# Main_Board.net
KiCad netlist of a schematic drawn in EAGLE
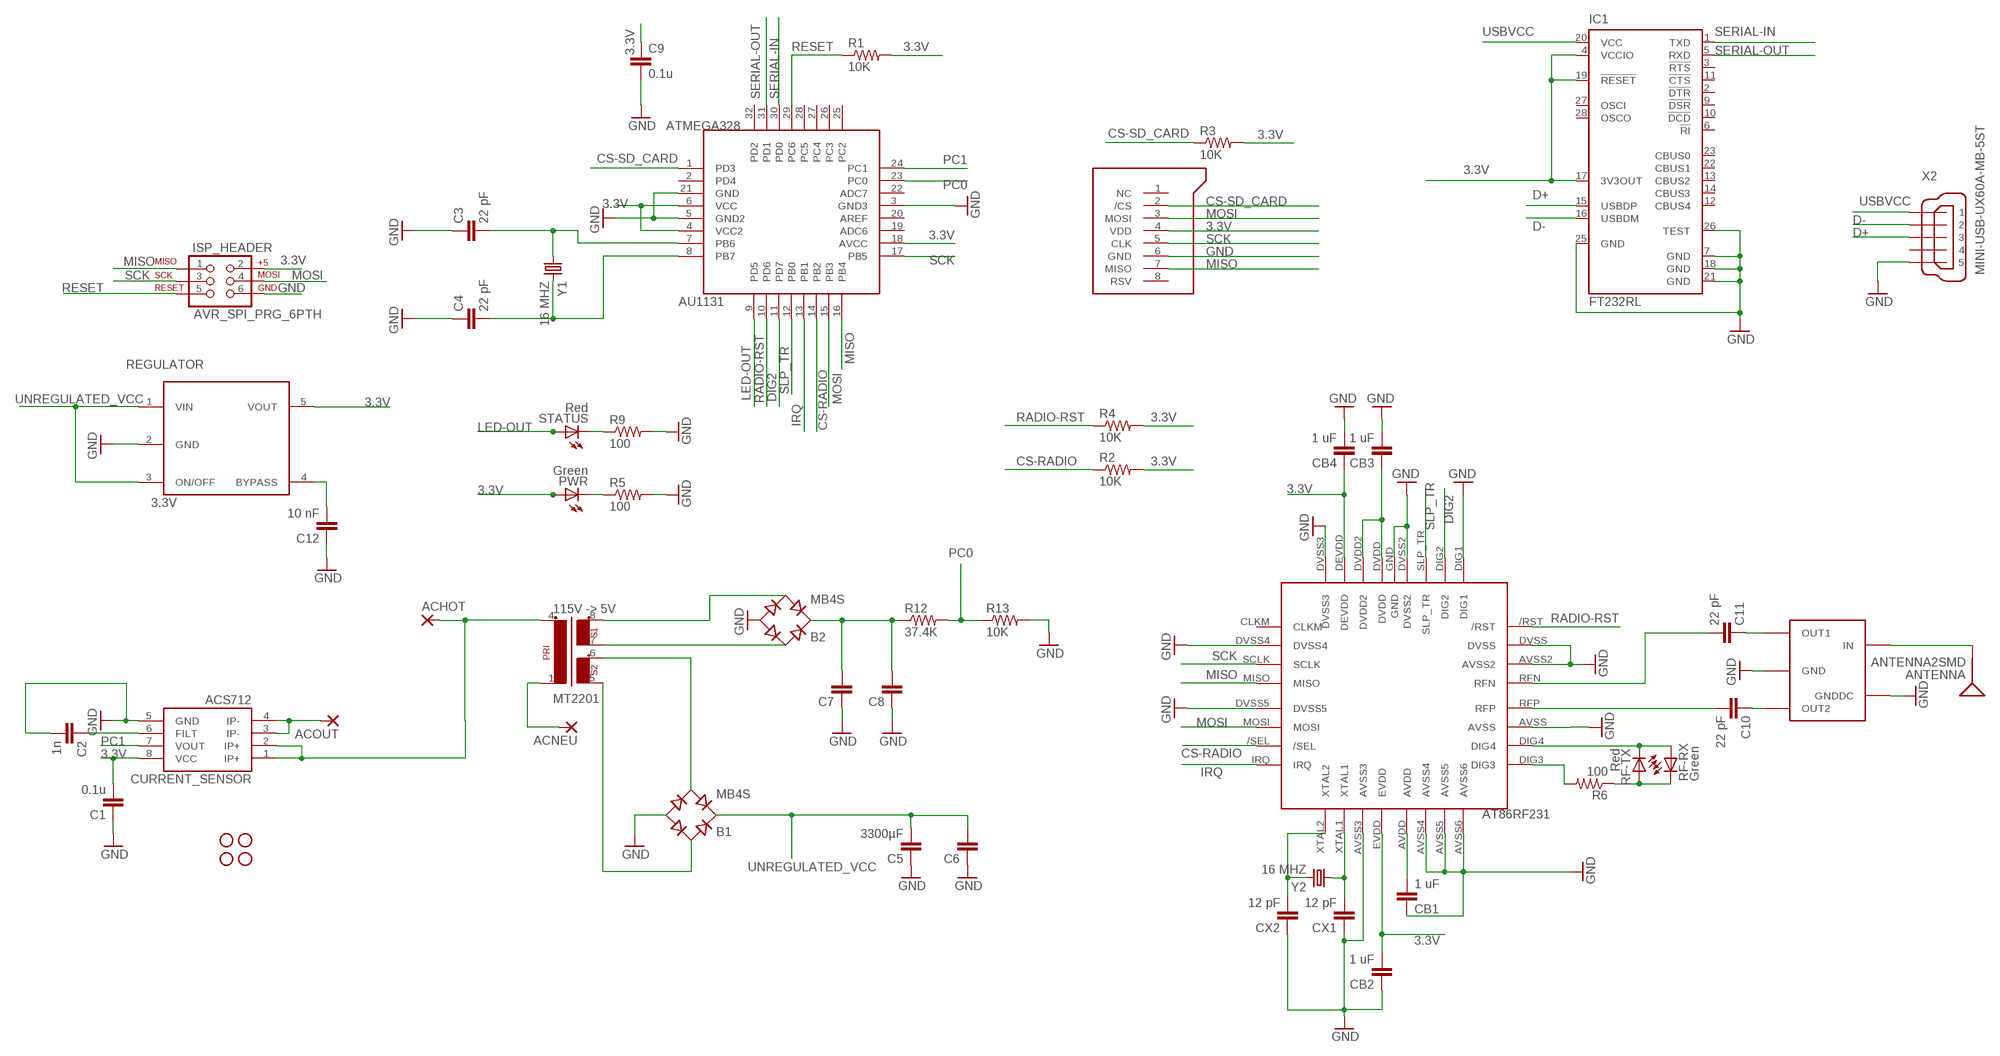
[diagram p0: schematic, sheet 1]

(export (version "E")
  (design (tool "Eeschema 10.0.6"))
  (components
    (comp (ref "3.3V_REGULATOR")
      (value "REG3.3V")
      (footprint "eagle-import:SOT23-5")
      (libsource (lib "eagle-import") (part "REG3.3V"))
    )
    (comp (ref "ACHOT")
      (value "PTH3MM")
      (footprint "eagle-import:PTH-3MM")
      (libsource (lib "eagle-import") (part "PTH3MM"))
    )
    (comp (ref "ACNEU")
      (value "PTH3MM")
      (footprint "eagle-import:PTH-3MM")
      (libsource (lib "eagle-import") (part "PTH3MM"))
    )
    (comp (ref "ACOUT")
      (value "PTH3MM")
      (footprint "eagle-import:PTH-3MM")
      (libsource (lib "eagle-import") (part "PTH3MM"))
    )
    (comp (ref "ANTENNA")
      (value "ANTENNA2SMD")
      (footprint "eagle-import:ANTENNA-CHIP2")
      (libsource (lib "eagle-import") (part "ANTENNA2SMD"))
    )
    (comp (ref "AT86RF231")
      (value "AT86RF231(RADIO)AT86RF231")
      (footprint "eagle-import:32QN2(RADIO)")
      (libsource (lib "eagle-import") (part "AT86RF231(RADIO)AT86RF231"))
    )
    (comp (ref "ATMEGA328")
      (value "ATMEGA32832A")
      (footprint "eagle-import:TQFP32-08")
      (libsource (lib "eagle-import") (part "ATMEGA32832A"))
    )
    (comp (ref "B1")
      (value "MB4S")
      (footprint "eagle-import:SOIC-4")
      (libsource (lib "eagle-import") (part "MBS4"))
    )
    (comp (ref "B2")
      (value "MB4S")
      (footprint "eagle-import:SOIC-4")
      (libsource (lib "eagle-import") (part "MBS4"))
    )
    (comp (ref "BALUN")
      (value "WE-BAL")
      (footprint "eagle-import:WE-BAL")
      (libsource (lib "eagle-import") (part "WE-BAL"))
    )
    (comp (ref "C1")
      (value "0.1u")
      (footprint "eagle-import:0603-CAP")
      (libsource (lib "eagle-import") (part "CAP0603-CAP"))
    )
    (comp (ref "C2")
      (value "1n")
      (footprint "eagle-import:0603-CAP")
      (libsource (lib "eagle-import") (part "CAP0603-CAP"))
    )
    (comp (ref "C3")
      (value "22 pF")
      (footprint "eagle-import:0603-CAP")
      (libsource (lib "eagle-import") (part "CAP0603-CAP"))
    )
    (comp (ref "C4")
      (value "22 pF")
      (footprint "eagle-import:0603-CAP")
      (libsource (lib "eagle-import") (part "CAP0603-CAP"))
    )
    (comp (ref "C5")
      (value "3300µF")
      (footprint "eagle-import:CAP-PTH-5MM")
      (libsource (lib "eagle-import") (part "CAPPTH1"))
    )
    (comp (ref "C6")
      (value "CAPPTH1")
      (footprint "eagle-import:CAP-PTH-5MM")
      (libsource (lib "eagle-import") (part "CAPPTH1"))
    )
    (comp (ref "C7")
      (value "CAPPTH1")
      (footprint "eagle-import:CAP-PTH-5MM")
      (libsource (lib "eagle-import") (part "CAPPTH1"))
    )
    (comp (ref "C8")
      (value "CAPPTH1")
      (footprint "eagle-import:CAP-PTH-5MM")
      (libsource (lib "eagle-import") (part "CAPPTH1"))
    )
    (comp (ref "C9")
      (value "0.1u")
      (footprint "eagle-import:0603-CAP")
      (libsource (lib "eagle-import") (part "CAP0603-CAP"))
    )
    (comp (ref "C10")
      (value "22 pF")
      (footprint "eagle-import:0603-CAP")
      (libsource (lib "eagle-import") (part "CAP0603-CAP"))
    )
    (comp (ref "C11")
      (value "22 pF")
      (footprint "eagle-import:0603-CAP")
      (libsource (lib "eagle-import") (part "CAP0603-CAP"))
    )
    (comp (ref "C12")
      (value "10 nF")
      (footprint "eagle-import:0603-CAP")
      (libsource (lib "eagle-import") (part "CAP0603-CAP"))
    )
    (comp (ref "CB1")
      (value "1 uF")
      (footprint "eagle-import:0603-CAP")
      (libsource (lib "eagle-import") (part "CAP0603-CAP"))
    )
    (comp (ref "CB2")
      (value "1 uF")
      (footprint "eagle-import:0603-CAP")
      (libsource (lib "eagle-import") (part "CAP0603-CAP"))
    )
    (comp (ref "CB3")
      (value "1 uF")
      (footprint "eagle-import:0603-CAP")
      (libsource (lib "eagle-import") (part "CAP0603-CAP"))
    )
    (comp (ref "CB4")
      (value "1 uF")
      (footprint "eagle-import:0603-CAP")
      (libsource (lib "eagle-import") (part "CAP0603-CAP"))
    )
    (comp (ref "CURRENT_SENSOR")
      (value "ACS712")
      (footprint "eagle-import:SO08")
      (libsource (lib "eagle-import") (part "ACS712"))
    )
    (comp (ref "CX1")
      (value "12 pF")
      (footprint "eagle-import:0603-CAP")
      (libsource (lib "eagle-import") (part "CAP0603-CAP"))
    )
    (comp (ref "CX2")
      (value "12 pF")
      (footprint "eagle-import:0603-CAP")
      (libsource (lib "eagle-import") (part "CAP0603-CAP"))
    )
    (comp (ref "IC1")
      (value "FT232RL")
      (footprint "eagle-import:SSOP28")
      (libsource (lib "eagle-import") (part "FT232RL"))
    )
    (comp (ref "ISP_HEADER")
      (value "AVR_SPI_PRG_6PTH")
      (footprint "eagle-import:2X3")
      (libsource (lib "eagle-import") (part "AVR_SPI_PRG_6PTH"))
    )
    (comp (ref "JP1")
      (value "STAND-OFF")
      (footprint "eagle-import:STAND-OFF")
      (libsource (lib "eagle-import") (part "STAND-OFF"))
    )
    (comp (ref "JP2")
      (value "STAND-OFF")
      (footprint "eagle-import:STAND-OFF")
      (libsource (lib "eagle-import") (part "STAND-OFF"))
    )
    (comp (ref "JP3")
      (value "STAND-OFF")
      (footprint "eagle-import:STAND-OFF")
      (libsource (lib "eagle-import") (part "STAND-OFF"))
    )
    (comp (ref "JP4")
      (value "STAND-OFF")
      (footprint "eagle-import:STAND-OFF")
      (libsource (lib "eagle-import") (part "STAND-OFF"))
    )
    (comp (ref "MICROSD")
      (value "MICROSD")
      (footprint "eagle-import:MICRO-SD-SOCKET-PP")
      (libsource (lib "eagle-import") (part "MICROSD"))
    )
    (comp (ref "MT2201")
      (value "115V -> 5V")
      (footprint "eagle-import:EI38-2")
      (libsource (lib "eagle-import") (part "EI38-2"))
    )
    (comp (ref "PWR")
      (value "Green")
      (footprint "eagle-import:LED-0603")
      (libsource (lib "eagle-import") (part "LED0603"))
    )
    (comp (ref "R1")
      (value "10K")
      (footprint "eagle-import:0603-RES")
      (libsource (lib "eagle-import") (part "RESISTOR0603-RES"))
    )
    (comp (ref "R2")
      (value "10K")
      (footprint "eagle-import:0603-RES")
      (libsource (lib "eagle-import") (part "RESISTOR0603-RES"))
    )
    (comp (ref "R3")
      (value "10K")
      (footprint "eagle-import:0603-RES")
      (libsource (lib "eagle-import") (part "RESISTOR0603-RES"))
    )
    (comp (ref "R4")
      (value "10K")
      (footprint "eagle-import:0603-RES")
      (libsource (lib "eagle-import") (part "RESISTOR0603-RES"))
    )
    (comp (ref "R5")
      (value "100")
      (footprint "eagle-import:0603-RES")
      (libsource (lib "eagle-import") (part "RESISTOR0603-RES"))
    )
    (comp (ref "R6")
      (value "100")
      (footprint "eagle-import:0603-RES")
      (libsource (lib "eagle-import") (part "RESISTOR0603-RES"))
    )
    (comp (ref "R9")
      (value "100")
      (footprint "eagle-import:0603-RES")
      (libsource (lib "eagle-import") (part "RESISTOR0603-RES"))
    )
    (comp (ref "R12")
      (value "37.4K")
      (footprint "eagle-import:0603-RES")
      (libsource (lib "eagle-import") (part "RESISTOR0603-RES"))
    )
    (comp (ref "R13")
      (value "10K")
      (footprint "eagle-import:0603-RES")
      (libsource (lib "eagle-import") (part "RESISTOR0603-RES"))
    )
    (comp (ref "RF-RX")
      (value "Green")
      (footprint "eagle-import:LED-0603")
      (libsource (lib "eagle-import") (part "LED0603"))
    )
    (comp (ref "RF-TX")
      (value "Red")
      (footprint "eagle-import:LED-0603")
      (libsource (lib "eagle-import") (part "LED0603"))
    )
    (comp (ref "STATUS")
      (value "Red")
      (footprint "eagle-import:LED-0603")
      (libsource (lib "eagle-import") (part "LED0603"))
    )
    (comp (ref "X2")
      (value "MINI-USB-UX60A-MB-5ST")
      (footprint "eagle-import:UX60A-MB-5ST")
      (libsource (lib "eagle-import") (part "MINI-USB-UX60A-MB-5ST"))
    )
    (comp (ref "Y1")
      (value "16 MHZ")
      (footprint "eagle-import:HC49UP")
      (libsource (lib "eagle-import") (part "CRYSTALSMD"))
    )
    (comp (ref "Y2")
      (value "16 MHZ")
      (footprint "eagle-import:HC49UP")
      (libsource (lib "eagle-import") (part "CRYSTALSMD"))
    )
  )
  (nets
    (net (code "1") (name "/3.3V") (class "Default")
      (node (ref "3.3V_REGULATOR") (pin "5") (pinfunction "VOUT_5") (pintype "bidirectional"))
      (node (ref "AT86RF231") (pin "DEVDD") (pinfunction "DEVDD_DEVDD") (pintype "bidirectional"))
      (node (ref "AT86RF231") (pin "EVDD") (pinfunction "EVDD_EVDD") (pintype "bidirectional"))
      (node (ref "ATMEGA328") (pin "18") (pinfunction "AVCC_18") (pintype "bidirectional"))
      (node (ref "ATMEGA328") (pin "4") (pinfunction "VCC2_4") (pintype "bidirectional"))
      (node (ref "ATMEGA328") (pin "6") (pinfunction "VCC_6") (pintype "bidirectional"))
      (node (ref "C1") (pin "2") (pinfunction "2_2") (pintype "passive"))
      (node (ref "C9") (pin "1") (pinfunction "1_1") (pintype "passive"))
      (node (ref "CB2") (pin "2") (pinfunction "2_2") (pintype "passive"))
      (node (ref "CB4") (pin "1") (pinfunction "1_1") (pintype "passive"))
      (node (ref "CURRENT_SENSOR") (pin "8") (pinfunction "VCC_8") (pintype "bidirectional"))
      (node (ref "IC1") (pin "17") (pinfunction "3V3OUT_17") (pintype "output"))
      (node (ref "IC1") (pin "19") (pinfunction "~{RESET}_19") (pintype "input"))
      (node (ref "IC1") (pin "4") (pinfunction "VCCIO_4") (pintype "power_in"))
      (node (ref "ISP_HEADER") (pin "2") (pinfunction "2_2") (pintype "passive"))
      (node (ref "MICROSD") (pin "4") (pinfunction "VDD_4") (pintype "bidirectional"))
      (node (ref "PWR") (pin "A") (pinfunction "A_A") (pintype "passive"))
      (node (ref "R1") (pin "2") (pinfunction "2_2") (pintype "passive"))
      (node (ref "R2") (pin "2") (pinfunction "2_2") (pintype "passive"))
      (node (ref "R3") (pin "2") (pinfunction "2_2") (pintype "passive"))
      (node (ref "R4") (pin "2") (pinfunction "2_2") (pintype "passive"))
    )
    (net (code "2") (name "/CS-RADIO") (class "Default")
      (node (ref "AT86RF231") (pin "/SEL") (pinfunction "/SEL_/SEL") (pintype "bidirectional"))
      (node (ref "ATMEGA328") (pin "14") (pinfunction "PB2_14") (pintype "bidirectional"))
      (node (ref "R2") (pin "1") (pinfunction "1_1") (pintype "passive"))
    )
    (net (code "3") (name "/CS-SD_CARD") (class "Default")
      (node (ref "ATMEGA328") (pin "1") (pinfunction "PD3_1") (pintype "bidirectional"))
      (node (ref "MICROSD") (pin "2") (pinfunction "/CS_2") (pintype "bidirectional"))
      (node (ref "R3") (pin "1") (pinfunction "1_1") (pintype "passive"))
    )
    (net (code "4") (name "/D+") (class "Default")
      (node (ref "IC1") (pin "15") (pinfunction "USBDP_15") (pintype "bidirectional"))
      (node (ref "X2") (pin "3") (pinfunction "3_3") (pintype "input"))
    )
    (net (code "5") (name "/D-") (class "Default")
      (node (ref "IC1") (pin "16") (pinfunction "USBDM_16") (pintype "bidirectional"))
      (node (ref "X2") (pin "2") (pinfunction "2_2") (pintype "input"))
    )
    (net (code "6") (name "/DIG2") (class "Default")
      (node (ref "AT86RF231") (pin "DIG2") (pinfunction "DIG2_DIG2") (pintype "bidirectional"))
      (node (ref "ATMEGA328") (pin "11") (pinfunction "PD7_11") (pintype "bidirectional"))
    )
    (net (code "7") (name "/IRQ") (class "Default")
      (node (ref "AT86RF231") (pin "IRQ") (pinfunction "IRQ_IRQ") (pintype "bidirectional"))
      (node (ref "ATMEGA328") (pin "13") (pinfunction "PB1_13") (pintype "bidirectional"))
    )
    (net (code "8") (name "/LED-OUT") (class "Default")
      (node (ref "ATMEGA328") (pin "9") (pinfunction "PD5_9") (pintype "bidirectional"))
      (node (ref "STATUS") (pin "A") (pinfunction "A_A") (pintype "passive"))
    )
    (net (code "9") (name "/MISO") (class "Default")
      (node (ref "AT86RF231") (pin "MISO") (pinfunction "MISO_MISO") (pintype "bidirectional"))
      (node (ref "ATMEGA328") (pin "16") (pinfunction "PB4_16") (pintype "bidirectional"))
      (node (ref "ISP_HEADER") (pin "1") (pinfunction "1_1") (pintype "passive"))
      (node (ref "MICROSD") (pin "7") (pinfunction "MISO_7") (pintype "bidirectional"))
    )
    (net (code "10") (name "/MOSI") (class "Default")
      (node (ref "AT86RF231") (pin "MOSI") (pinfunction "MOSI_MOSI") (pintype "bidirectional"))
      (node (ref "ATMEGA328") (pin "15") (pinfunction "PB3_15") (pintype "bidirectional"))
      (node (ref "ISP_HEADER") (pin "4") (pinfunction "4_4") (pintype "passive"))
      (node (ref "MICROSD") (pin "3") (pinfunction "MOSI_3") (pintype "bidirectional"))
    )
    (net (code "11") (name "/PC0") (class "Default")
      (node (ref "ATMEGA328") (pin "23") (pinfunction "PC0_23") (pintype "bidirectional"))
      (node (ref "R12") (pin "2") (pinfunction "2_2") (pintype "passive"))
      (node (ref "R13") (pin "1") (pinfunction "1_1") (pintype "passive"))
    )
    (net (code "12") (name "/PC1") (class "Default")
      (node (ref "ATMEGA328") (pin "24") (pinfunction "PC1_24") (pintype "bidirectional"))
      (node (ref "CURRENT_SENSOR") (pin "7") (pinfunction "VOUT_7") (pintype "bidirectional"))
    )
    (net (code "13") (name "/RADIO-RST") (class "Default")
      (node (ref "AT86RF231") (pin "/RST") (pinfunction "/RST_/RST") (pintype "bidirectional"))
      (node (ref "ATMEGA328") (pin "10") (pinfunction "PD6_10") (pintype "bidirectional"))
      (node (ref "R4") (pin "1") (pinfunction "1_1") (pintype "passive"))
    )
    (net (code "14") (name "/RESET") (class "Default")
      (node (ref "ATMEGA328") (pin "29") (pinfunction "PC6_29") (pintype "bidirectional"))
      (node (ref "ISP_HEADER") (pin "5") (pinfunction "5_5") (pintype "passive"))
      (node (ref "R1") (pin "1") (pinfunction "1_1") (pintype "passive"))
    )
    (net (code "15") (name "/SCK") (class "Default")
      (node (ref "AT86RF231") (pin "SCLK") (pinfunction "SCLK_SCLK") (pintype "bidirectional"))
      (node (ref "ATMEGA328") (pin "17") (pinfunction "PB5_17") (pintype "bidirectional"))
      (node (ref "ISP_HEADER") (pin "3") (pinfunction "3_3") (pintype "passive"))
      (node (ref "MICROSD") (pin "5") (pinfunction "CLK_5") (pintype "bidirectional"))
    )
    (net (code "16") (name "/SERIAL-IN") (class "Default")
      (node (ref "ATMEGA328") (pin "30") (pinfunction "PD0_30") (pintype "bidirectional"))
      (node (ref "IC1") (pin "1") (pinfunction "TXD_1") (pintype "output"))
    )
    (net (code "17") (name "/SERIAL-OUT") (class "Default")
      (node (ref "ATMEGA328") (pin "31") (pinfunction "PD1_31") (pintype "bidirectional"))
      (node (ref "IC1") (pin "5") (pinfunction "RXD_5") (pintype "input"))
    )
    (net (code "18") (name "/SLP_TR") (class "Default")
      (node (ref "AT86RF231") (pin "SLP_TR") (pinfunction "SLP_TR_SLP_TR") (pintype "bidirectional"))
      (node (ref "ATMEGA328") (pin "12") (pinfunction "PB0_12") (pintype "bidirectional"))
    )
    (net (code "19") (name "/UNREGULATED_VCC") (class "Default")
      (node (ref "3.3V_REGULATOR") (pin "1") (pinfunction "VIN_1") (pintype "bidirectional"))
      (node (ref "3.3V_REGULATOR") (pin "3") (pinfunction "ON/OFF_3") (pintype "bidirectional"))
      (node (ref "B1") (pin "+") (pinfunction "+_+") (pintype "passive"))
      (node (ref "C5") (pin "2") (pinfunction "2_2") (pintype "passive"))
      (node (ref "C6") (pin "2") (pinfunction "2_2") (pintype "passive"))
    )
    (net (code "20") (name "/USBVCC") (class "Default")
      (node (ref "IC1") (pin "20") (pinfunction "VCC_20") (pintype "power_in"))
      (node (ref "X2") (pin "1") (pinfunction "1_1") (pintype "input"))
    )
    (net (code "21") (name "GND") (class "Default")
      (node (ref "3.3V_REGULATOR") (pin "2") (pinfunction "GND_2") (pintype "bidirectional"))
      (node (ref "AT86RF231") (pin "AVSS") (pinfunction "AVSS_AVSS") (pintype "bidirectional"))
      (node (ref "AT86RF231") (pin "AVSS2") (pinfunction "AVSS2_AVSS2") (pintype "bidirectional"))
      (node (ref "AT86RF231") (pin "AVSS3") (pinfunction "AVSS3_AVSS3") (pintype "bidirectional"))
      (node (ref "AT86RF231") (pin "AVSS4") (pinfunction "AVSS4_AVSS4") (pintype "bidirectional"))
      (node (ref "AT86RF231") (pin "AVSS5") (pinfunction "AVSS5_AVSS5") (pintype "bidirectional"))
      (node (ref "AT86RF231") (pin "AVSS6") (pinfunction "AVSS6_AVSS6") (pintype "bidirectional"))
      (node (ref "AT86RF231") (pin "DIG1") (pinfunction "DIG1_DIG1") (pintype "bidirectional"))
      (node (ref "AT86RF231") (pin "DVSS") (pinfunction "DVSS_DVSS") (pintype "bidirectional"))
      (node (ref "AT86RF231") (pin "DVSS2") (pinfunction "DVSS2_DVSS2") (pintype "bidirectional"))
      (node (ref "AT86RF231") (pin "DVSS3") (pinfunction "DVSS3_DVSS3") (pintype "bidirectional"))
      (node (ref "AT86RF231") (pin "DVSS4") (pinfunction "DVSS4_DVSS4") (pintype "bidirectional"))
      (node (ref "AT86RF231") (pin "DVSS5") (pinfunction "DVSS5_DVSS5") (pintype "bidirectional"))
      (node (ref "AT86RF231") (pin "GND") (pinfunction "GND_GND") (pintype "bidirectional"))
      (node (ref "ATMEGA328") (pin "21") (pinfunction "GND_21") (pintype "bidirectional"))
      (node (ref "ATMEGA328") (pin "3") (pinfunction "GND3_3") (pintype "bidirectional"))
      (node (ref "ATMEGA328") (pin "5") (pinfunction "GND2_5") (pintype "bidirectional"))
      (node (ref "B1") (pin "-") (pinfunction "-_-") (pintype "passive"))
      (node (ref "B2") (pin "-") (pinfunction "-_-") (pintype "passive"))
      (node (ref "BALUN") (pin "GND") (pinfunction "GND_GND") (pintype "bidirectional"))
      (node (ref "BALUN") (pin "GNDDC") (pinfunction "GNDDC_GNDDC") (pintype "bidirectional"))
      (node (ref "C1") (pin "1") (pinfunction "1_1") (pintype "passive"))
      (node (ref "C12") (pin "1") (pinfunction "1_1") (pintype "passive"))
      (node (ref "C2") (pin "2") (pinfunction "2_2") (pintype "passive"))
      (node (ref "C3") (pin "1") (pinfunction "1_1") (pintype "passive"))
      (node (ref "C4") (pin "1") (pinfunction "1_1") (pintype "passive"))
      (node (ref "C5") (pin "1") (pinfunction "1_1") (pintype "passive"))
      (node (ref "C6") (pin "1") (pinfunction "1_1") (pintype "passive"))
      (node (ref "C7") (pin "1") (pinfunction "1_1") (pintype "passive"))
      (node (ref "C8") (pin "1") (pinfunction "1_1") (pintype "passive"))
      (node (ref "C9") (pin "2") (pinfunction "2_2") (pintype "passive"))
      (node (ref "CB1") (pin "1") (pinfunction "1_1") (pintype "passive"))
      (node (ref "CB2") (pin "1") (pinfunction "1_1") (pintype "passive"))
      (node (ref "CB3") (pin "2") (pinfunction "2_2") (pintype "passive"))
      (node (ref "CB4") (pin "2") (pinfunction "2_2") (pintype "passive"))
      (node (ref "CURRENT_SENSOR") (pin "5") (pinfunction "GND_5") (pintype "bidirectional"))
      (node (ref "CX1") (pin "1") (pinfunction "1_1") (pintype "passive"))
      (node (ref "CX2") (pin "1") (pinfunction "1_1") (pintype "passive"))
      (node (ref "IC1") (pin "18") (pinfunction "GND_18") (pintype "power_in"))
      (node (ref "IC1") (pin "21") (pinfunction "GND_21") (pintype "power_in"))
      (node (ref "IC1") (pin "25") (pinfunction "GND_25") (pintype "power_in"))
      (node (ref "IC1") (pin "26") (pinfunction "TEST_26") (pintype "input"))
      (node (ref "IC1") (pin "7") (pinfunction "GND_7") (pintype "power_in"))
      (node (ref "ISP_HEADER") (pin "6") (pinfunction "6_6") (pintype "passive"))
      (node (ref "MICROSD") (pin "6") (pinfunction "GND_6") (pintype "bidirectional"))
      (node (ref "R13") (pin "2") (pinfunction "2_2") (pintype "passive"))
      (node (ref "R5") (pin "2") (pinfunction "2_2") (pintype "passive"))
      (node (ref "R9") (pin "2") (pinfunction "2_2") (pintype "passive"))
      (node (ref "X2") (pin "5") (pinfunction "5_5") (pintype "input"))
    )
    (net (code "22") (name "Net-(3.3V_REGULATOR-BYPASS)") (class "Default")
      (node (ref "3.3V_REGULATOR") (pin "4") (pinfunction "BYPASS_4") (pintype "bidirectional"))
      (node (ref "C12") (pin "2") (pinfunction "2_2") (pintype "passive"))
    )
    (net (code "23") (name "Net-(ACHOT-P)") (class "Default")
      (node (ref "ACHOT") (pin "1") (pinfunction "P_1") (pintype "passive"))
      (node (ref "CURRENT_SENSOR") (pin "1") (pinfunction "IP+_1") (pintype "bidirectional"))
      (node (ref "CURRENT_SENSOR") (pin "2") (pinfunction "IP+_2") (pintype "bidirectional"))
      (node (ref "MT2201") (pin "4") (pinfunction "4_4") (pintype "passive"))
    )
    (net (code "24") (name "Net-(ACNEU-P)") (class "Default")
      (node (ref "ACNEU") (pin "1") (pinfunction "P_1") (pintype "passive"))
      (node (ref "MT2201") (pin "1") (pinfunction "1_1") (pintype "passive"))
    )
    (net (code "25") (name "Net-(ACOUT-P)") (class "Default")
      (node (ref "ACOUT") (pin "1") (pinfunction "P_1") (pintype "passive"))
      (node (ref "CURRENT_SENSOR") (pin "3") (pinfunction "IP-_3") (pintype "bidirectional"))
      (node (ref "CURRENT_SENSOR") (pin "4") (pinfunction "IP-_4") (pintype "bidirectional"))
    )
    (net (code "26") (name "Net-(ANTENNA-SIGNAL)") (class "Default")
      (node (ref "ANTENNA") (pin "FEED") (pinfunction "SIGNAL_FEED") (pintype "bidirectional"))
      (node (ref "BALUN") (pin "IN") (pinfunction "IN_IN") (pintype "bidirectional"))
    )
    (net (code "27") (name "Net-(AT86RF231-PadAVDD)") (class "Default")
      (node (ref "AT86RF231") (pin "AVDD") (pinfunction "AVDD_AVDD") (pintype "bidirectional"))
      (node (ref "CB1") (pin "2") (pinfunction "2_2") (pintype "passive"))
    )
    (net (code "28") (name "Net-(AT86RF231-PadDIG3)") (class "Default")
      (node (ref "AT86RF231") (pin "DIG3") (pinfunction "DIG3_DIG3") (pintype "bidirectional"))
      (node (ref "R6") (pin "2") (pinfunction "2_2") (pintype "passive"))
    )
    (net (code "29") (name "Net-(AT86RF231-PadDIG4)") (class "Default")
      (node (ref "AT86RF231") (pin "DIG4") (pinfunction "DIG4_DIG4") (pintype "bidirectional"))
      (node (ref "RF-RX") (pin "A") (pinfunction "A_A") (pintype "passive"))
      (node (ref "RF-TX") (pin "C") (pinfunction "C_C") (pintype "passive"))
    )
    (net (code "30") (name "Net-(AT86RF231-PadDVDD)") (class "Default")
      (node (ref "AT86RF231") (pin "DVDD") (pinfunction "DVDD_DVDD") (pintype "bidirectional"))
      (node (ref "AT86RF231") (pin "DVDD2") (pinfunction "DVDD2_DVDD2") (pintype "bidirectional"))
      (node (ref "CB3") (pin "1") (pinfunction "1_1") (pintype "passive"))
    )
    (net (code "31") (name "Net-(AT86RF231-PadRFN)") (class "Default")
      (node (ref "AT86RF231") (pin "RFN") (pinfunction "RFN_RFN") (pintype "bidirectional"))
      (node (ref "C11") (pin "2") (pinfunction "2_2") (pintype "passive"))
    )
    (net (code "32") (name "Net-(AT86RF231-PadRFP)") (class "Default")
      (node (ref "AT86RF231") (pin "RFP") (pinfunction "RFP_RFP") (pintype "bidirectional"))
      (node (ref "C10") (pin "2") (pinfunction "2_2") (pintype "passive"))
    )
    (net (code "33") (name "Net-(AT86RF231-PadXTAL1)") (class "Default")
      (node (ref "AT86RF231") (pin "XTAL1") (pinfunction "XTAL1_XTAL1") (pintype "bidirectional"))
      (node (ref "CX1") (pin "2") (pinfunction "2_2") (pintype "passive"))
      (node (ref "Y2") (pin "1") (pinfunction "1_1") (pintype "passive"))
    )
    (net (code "34") (name "Net-(AT86RF231-PadXTAL2)") (class "Default")
      (node (ref "AT86RF231") (pin "XTAL2") (pinfunction "XTAL2_XTAL2") (pintype "bidirectional"))
      (node (ref "CX2") (pin "2") (pinfunction "2_2") (pintype "passive"))
      (node (ref "Y2") (pin "2") (pinfunction "2_2") (pintype "passive"))
    )
    (net (code "35") (name "Net-(ATMEGA328-PB6)") (class "Default")
      (node (ref "ATMEGA328") (pin "7") (pinfunction "PB6_7") (pintype "bidirectional"))
      (node (ref "C3") (pin "2") (pinfunction "2_2") (pintype "passive"))
      (node (ref "Y1") (pin "1") (pinfunction "1_1") (pintype "passive"))
    )
    (net (code "36") (name "Net-(ATMEGA328-PB7)") (class "Default")
      (node (ref "ATMEGA328") (pin "8") (pinfunction "PB7_8") (pintype "bidirectional"))
      (node (ref "C4") (pin "2") (pinfunction "2_2") (pintype "passive"))
      (node (ref "Y1") (pin "2") (pinfunction "2_2") (pintype "passive"))
    )
    (net (code "37") (name "Net-(B1-AC1)") (class "Default")
      (node (ref "B1") (pin "~1") (pinfunction "AC1_~1") (pintype "passive"))
      (node (ref "MT2201") (pin "5") (pinfunction "5_5") (pintype "passive"))
    )
    (net (code "38") (name "Net-(B1-AC2)") (class "Default")
      (node (ref "B1") (pin "~2") (pinfunction "AC2_~2") (pintype "passive"))
      (node (ref "MT2201") (pin "6") (pinfunction "6_6") (pintype "passive"))
    )
    (net (code "39") (name "Net-(B2-AC1)") (class "Default")
      (node (ref "B2") (pin "~1") (pinfunction "AC1_~1") (pintype "passive"))
      (node (ref "MT2201") (pin "7") (pinfunction "7_7") (pintype "passive"))
    )
    (net (code "40") (name "Net-(B2-AC2)") (class "Default")
      (node (ref "B2") (pin "~2") (pinfunction "AC2_~2") (pintype "passive"))
      (node (ref "MT2201") (pin "8") (pinfunction "8_8") (pintype "passive"))
    )
    (net (code "41") (name "Net-(B2-Pad+)") (class "Default")
      (node (ref "B2") (pin "+") (pinfunction "+_+") (pintype "passive"))
      (node (ref "C7") (pin "2") (pinfunction "2_2") (pintype "passive"))
      (node (ref "C8") (pin "2") (pinfunction "2_2") (pintype "passive"))
      (node (ref "R12") (pin "1") (pinfunction "1_1") (pintype "passive"))
    )
    (net (code "42") (name "Net-(BALUN-PadOUT1)") (class "Default")
      (node (ref "BALUN") (pin "OUT1") (pinfunction "OUT1_OUT1") (pintype "bidirectional"))
      (node (ref "C11") (pin "1") (pinfunction "1_1") (pintype "passive"))
    )
    (net (code "43") (name "Net-(BALUN-PadOUT2)") (class "Default")
      (node (ref "BALUN") (pin "OUT2") (pinfunction "OUT2_OUT2") (pintype "bidirectional"))
      (node (ref "C10") (pin "1") (pinfunction "1_1") (pintype "passive"))
    )
    (net (code "44") (name "Net-(CURRENT_SENSOR-FILT)") (class "Default")
      (node (ref "C2") (pin "1") (pinfunction "1_1") (pintype "passive"))
      (node (ref "CURRENT_SENSOR") (pin "6") (pinfunction "FILT_6") (pintype "bidirectional"))
    )
    (net (code "45") (name "Net-(PWR-PadC)") (class "Default")
      (node (ref "PWR") (pin "C") (pinfunction "C_C") (pintype "passive"))
      (node (ref "R5") (pin "1") (pinfunction "1_1") (pintype "passive"))
    )
    (net (code "46") (name "Net-(R6-Pad1)") (class "Default")
      (node (ref "R6") (pin "1") (pinfunction "1_1") (pintype "passive"))
      (node (ref "RF-RX") (pin "C") (pinfunction "C_C") (pintype "passive"))
      (node (ref "RF-TX") (pin "A") (pinfunction "A_A") (pintype "passive"))
    )
    (net (code "47") (name "Net-(R9-Pad1)") (class "Default")
      (node (ref "R9") (pin "1") (pinfunction "1_1") (pintype "passive"))
      (node (ref "STATUS") (pin "C") (pinfunction "C_C") (pintype "passive"))
    )
    (net (code "48") (name "unconnected-(AT86RF231-PadCLKM)") (class "Default")
      (node (ref "AT86RF231") (pin "CLKM") (pinfunction "CLKM_CLKM") (pintype "bidirectional"))
    )
    (net (code "49") (name "unconnected-(ATMEGA328-ADC6-Pad19)") (class "Default")
      (node (ref "ATMEGA328") (pin "19") (pinfunction "ADC6_19") (pintype "bidirectional"))
    )
    (net (code "50") (name "unconnected-(ATMEGA328-ADC7-Pad22)") (class "Default")
      (node (ref "ATMEGA328") (pin "22") (pinfunction "ADC7_22") (pintype "bidirectional"))
    )
    (net (code "51") (name "unconnected-(ATMEGA328-AREF-Pad20)") (class "Default")
      (node (ref "ATMEGA328") (pin "20") (pinfunction "AREF_20") (pintype "bidirectional"))
    )
    (net (code "52") (name "unconnected-(ATMEGA328-PC2-Pad25)") (class "Default")
      (node (ref "ATMEGA328") (pin "25") (pinfunction "PC2_25") (pintype "bidirectional"))
    )
    (net (code "53") (name "unconnected-(ATMEGA328-PC3-Pad26)") (class "Default")
      (node (ref "ATMEGA328") (pin "26") (pinfunction "PC3_26") (pintype "bidirectional"))
    )
    (net (code "54") (name "unconnected-(ATMEGA328-PC4-Pad27)") (class "Default")
      (node (ref "ATMEGA328") (pin "27") (pinfunction "PC4_27") (pintype "bidirectional"))
    )
    (net (code "55") (name "unconnected-(ATMEGA328-PC5-Pad28)") (class "Default")
      (node (ref "ATMEGA328") (pin "28") (pinfunction "PC5_28") (pintype "bidirectional"))
    )
    (net (code "56") (name "unconnected-(ATMEGA328-PD2-Pad32)") (class "Default")
      (node (ref "ATMEGA328") (pin "32") (pinfunction "PD2_32") (pintype "bidirectional"))
    )
    (net (code "57") (name "unconnected-(ATMEGA328-PD4-Pad2)") (class "Default")
      (node (ref "ATMEGA328") (pin "2") (pinfunction "PD4_2") (pintype "bidirectional"))
    )
    (net (code "58") (name "unconnected-(IC1-CBUS0-Pad23)") (class "Default")
      (node (ref "IC1") (pin "23") (pinfunction "CBUS0_23") (pintype "bidirectional"))
    )
    (net (code "59") (name "unconnected-(IC1-CBUS1-Pad22)") (class "Default")
      (node (ref "IC1") (pin "22") (pinfunction "CBUS1_22") (pintype "bidirectional"))
    )
    (net (code "60") (name "unconnected-(IC1-CBUS2-Pad13)") (class "Default")
      (node (ref "IC1") (pin "13") (pinfunction "CBUS2_13") (pintype "bidirectional"))
    )
    (net (code "61") (name "unconnected-(IC1-CBUS3-Pad14)") (class "Default")
      (node (ref "IC1") (pin "14") (pinfunction "CBUS3_14") (pintype "bidirectional"))
    )
    (net (code "62") (name "unconnected-(IC1-CBUS4-Pad12)") (class "Default")
      (node (ref "IC1") (pin "12") (pinfunction "CBUS4_12") (pintype "bidirectional"))
    )
    (net (code "63") (name "unconnected-(IC1-OSCI-Pad27)") (class "Default")
      (node (ref "IC1") (pin "27") (pinfunction "OSCI_27") (pintype "input"))
    )
    (net (code "64") (name "unconnected-(IC1-OSCO-Pad28)") (class "Default")
      (node (ref "IC1") (pin "28") (pinfunction "OSCO_28") (pintype "output"))
    )
    (net (code "65") (name "unconnected-(IC1-~{CTS}-Pad11)") (class "Default")
      (node (ref "IC1") (pin "11") (pinfunction "~{CTS}_11") (pintype "input"))
    )
    (net (code "66") (name "unconnected-(IC1-~{DCD}-Pad10)") (class "Default")
      (node (ref "IC1") (pin "10") (pinfunction "~{DCD}_10") (pintype "input"))
    )
    (net (code "67") (name "unconnected-(IC1-~{DSR}-Pad9)") (class "Default")
      (node (ref "IC1") (pin "9") (pinfunction "~{DSR}_9") (pintype "input"))
    )
    (net (code "68") (name "unconnected-(IC1-~{DTR}-Pad2)") (class "Default")
      (node (ref "IC1") (pin "2") (pinfunction "~{DTR}_2") (pintype "output"))
    )
    (net (code "69") (name "unconnected-(IC1-~{RI}-Pad6)") (class "Default")
      (node (ref "IC1") (pin "6") (pinfunction "~{RI}_6") (pintype "input"))
    )
    (net (code "70") (name "unconnected-(IC1-~{RTS}-Pad3)") (class "Default")
      (node (ref "IC1") (pin "3") (pinfunction "~{RTS}_3") (pintype "output"))
    )
    (net (code "71") (name "unconnected-(MICROSD-NC-Pad1)") (class "Default")
      (node (ref "MICROSD") (pin "1") (pinfunction "NC_1") (pintype "bidirectional"))
    )
    (net (code "72") (name "unconnected-(MICROSD-RSV-Pad8)") (class "Default")
      (node (ref "MICROSD") (pin "8") (pinfunction "RSV_8") (pintype "bidirectional"))
    )
    (net (code "73") (name "unconnected-(X2-Pad4)") (class "Default")
      (node (ref "X2") (pin "4") (pinfunction "4_4") (pintype "input"))
    )
  )
)
